# HMC1053-cell.net
KiCad netlist of a schematic drawn in Altium Designer
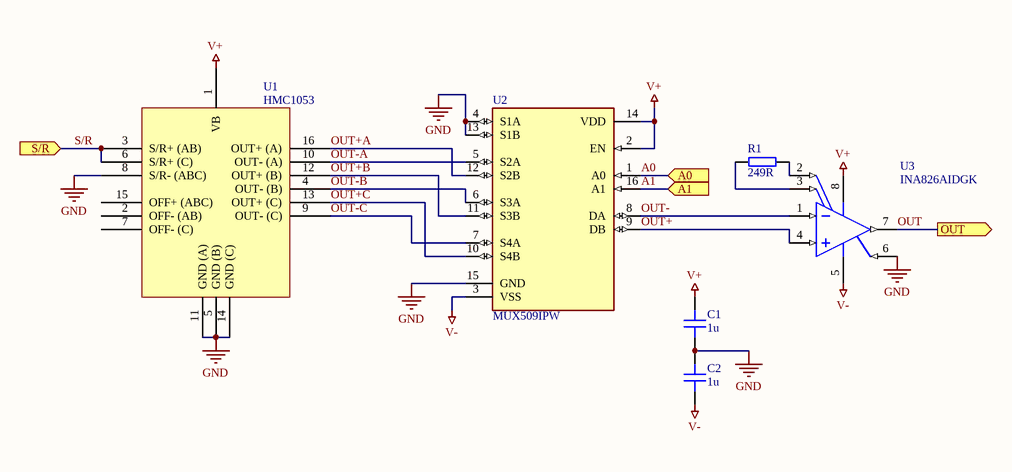
[diagram p0: HMC1053-cell.SchDoc]

(export (version "E")
  (design (tool "Eeschema 10.0.6"))
  (components
    (comp (ref "C1")
      (value "1u")
      (footprint "CAP_0402")
      (description "Capacitor SMD 0402")
      (fields (field (name "VOLTAGE") "50V"))
      (libsource (lib "symbols") (part "CAP_0402"))
    )
    (comp (ref "C2")
      (value "1u")
      (footprint "CAP_0402")
      (description "Capacitor SMD 0402")
      (fields (field (name "VOLTAGE") "50V"))
      (libsource (lib "symbols") (part "CAP_0402"))
    )
    (comp (ref "R1")
      (value "249R")
      (footprint "RES_0402")
      (description "Resistor SMD 0402")
      (libsource (lib "symbols") (part "RES_0402"))
    )
    (comp (ref "U1")
      (value "HMC1053")
      (footprint "HMC1053")
      (description "3-axis magnetoresistive sensor")
      (fields (field (name "MANUFACTURER") "Honeywell"))
      (libsource (lib "symbols") (part "HMC1053"))
    )
    (comp (ref "U2")
      (value "MUX509IPW")
      (footprint "MUX509IPW")
      (description "IC MUX DUAL 4:1 170 OHM 16TSSOP")
      (libsource (lib "symbols") (part "MUX509IPW"))
    )
    (comp (ref "U3")
      (value "INA826AIDGK")
      (footprint "INA826AIDGK")
      (fields (field (name "MANUFACTURER") "Texas Instruments"))
      (libsource (lib "symbols") (part "INA826AIDGK"))
    )
  )
  (nets
    (net (code "1") (name "/A0") (class "Default")
      (node (ref "U2") (pin "1") (pinfunction "A0_1") (pintype "input"))
    )
    (net (code "2") (name "/A1") (class "Default")
      (node (ref "U2") (pin "16") (pinfunction "A1_16") (pintype "input"))
    )
    (net (code "3") (name "/OUT") (class "Default")
      (node (ref "U3") (pin "7") (pinfunction "VOUT_7") (pintype "output"))
    )
    (net (code "4") (name "/OUT+") (class "Default")
      (node (ref "U2") (pin "9") (pinfunction "DB_9") (pintype "bidirectional"))
      (node (ref "U3") (pin "4") (pinfunction "IN+_4") (pintype "input"))
    )
    (net (code "5") (name "/OUT+A") (class "Default")
      (node (ref "U1") (pin "16") (pinfunction "OUT+_(A)_16") (pintype "passive"))
      (node (ref "U2") (pin "12") (pinfunction "S2B_12") (pintype "bidirectional"))
    )
    (net (code "6") (name "/OUT+B") (class "Default")
      (node (ref "U1") (pin "12") (pinfunction "OUT+_(B)_12") (pintype "passive"))
      (node (ref "U2") (pin "11") (pinfunction "S3B_11") (pintype "bidirectional"))
    )
    (net (code "7") (name "/OUT+C") (class "Default")
      (node (ref "U1") (pin "13") (pinfunction "OUT+_(C)_13") (pintype "passive"))
      (node (ref "U2") (pin "10") (pinfunction "S4B_10") (pintype "bidirectional"))
    )
    (net (code "8") (name "/OUT-") (class "Default")
      (node (ref "U2") (pin "8") (pinfunction "DA_8") (pintype "bidirectional"))
      (node (ref "U3") (pin "1") (pinfunction "IN-_1") (pintype "input"))
    )
    (net (code "9") (name "/OUT-A") (class "Default")
      (node (ref "U1") (pin "10") (pinfunction "OUT-_(A)_10") (pintype "passive"))
      (node (ref "U2") (pin "5") (pinfunction "S2A_5") (pintype "bidirectional"))
    )
    (net (code "10") (name "/OUT-B") (class "Default")
      (node (ref "U1") (pin "4") (pinfunction "OUT-_(B)_4") (pintype "passive"))
      (node (ref "U2") (pin "6") (pinfunction "S3A_6") (pintype "bidirectional"))
    )
    (net (code "11") (name "/OUT-C") (class "Default")
      (node (ref "U1") (pin "9") (pinfunction "OUT-_(C)_9") (pintype "passive"))
      (node (ref "U2") (pin "7") (pinfunction "S4A_7") (pintype "bidirectional"))
    )
    (net (code "12") (name "/S{slash}R") (class "Default")
      (node (ref "U1") (pin "3") (pinfunction "S/R+_(AB)_3") (pintype "passive"))
      (node (ref "U1") (pin "6") (pinfunction "S/R+_(C)_6") (pintype "passive"))
    )
    (net (code "13") (name "GND") (class "Default")
      (node (ref "C1") (pin "1") (pinfunction "1_1") (pintype "passive"))
      (node (ref "C2") (pin "2") (pinfunction "2_2") (pintype "passive"))
      (node (ref "U1") (pin "11") (pinfunction "GND_(A)_11") (pintype "power_in"))
      (node (ref "U1") (pin "14") (pinfunction "GND_(C)_14") (pintype "power_in"))
      (node (ref "U1") (pin "5") (pinfunction "GND_(B)_5") (pintype "power_in"))
      (node (ref "U1") (pin "8") (pinfunction "S/R-_(ABC)_8") (pintype "passive"))
      (node (ref "U2") (pin "13") (pinfunction "S1B_13") (pintype "bidirectional"))
      (node (ref "U2") (pin "15") (pinfunction "GND_15") (pintype "power_in"))
      (node (ref "U2") (pin "4") (pinfunction "S1A_4") (pintype "bidirectional"))
      (node (ref "U3") (pin "6") (pinfunction "REF_6") (pintype "input"))
    )
    (net (code "14") (name "Net-(R1-Pad1)") (class "Default")
      (node (ref "R1") (pin "1") (pinfunction "1_1") (pintype "passive"))
      (node (ref "U3") (pin "2") (pinfunction "RG_2") (pintype "input"))
    )
    (net (code "15") (name "Net-(R1-Pad2)") (class "Default")
      (node (ref "R1") (pin "2") (pinfunction "2_2") (pintype "passive"))
      (node (ref "U3") (pin "3") (pinfunction "RG_3") (pintype "input"))
    )
    (net (code "16") (name "V+") (class "Default")
      (node (ref "C1") (pin "2") (pinfunction "2_2") (pintype "passive"))
      (node (ref "U1") (pin "1") (pinfunction "VB_1") (pintype "power_in"))
      (node (ref "U2") (pin "14") (pinfunction "VDD_14") (pintype "power_in"))
      (node (ref "U2") (pin "2") (pinfunction "EN_2") (pintype "input"))
      (node (ref "U3") (pin "8") (pinfunction "VS+_8") (pintype "power_in"))
    )
    (net (code "17") (name "V-") (class "Default")
      (node (ref "C2") (pin "1") (pinfunction "1_1") (pintype "passive"))
      (node (ref "U2") (pin "3") (pinfunction "VSS_3") (pintype "power_in"))
      (node (ref "U3") (pin "5") (pinfunction "VS-_5") (pintype "power_in"))
    )
    (net (code "18") (name "unconnected-(U1-OFF+_(ABC)-Pad15)") (class "Default")
      (node (ref "U1") (pin "15") (pinfunction "OFF+_(ABC)_15") (pintype "passive"))
    )
    (net (code "19") (name "unconnected-(U1-OFF-_(AB)-Pad2)") (class "Default")
      (node (ref "U1") (pin "2") (pinfunction "OFF-_(AB)_2") (pintype "passive"))
    )
    (net (code "20") (name "unconnected-(U1-OFF-_(C)-Pad7)") (class "Default")
      (node (ref "U1") (pin "7") (pinfunction "OFF-_(C)_7") (pintype "passive"))
    )
  )
)
